# elmett_shield.net
KiCad netlist of a schematic drawn in EAGLE
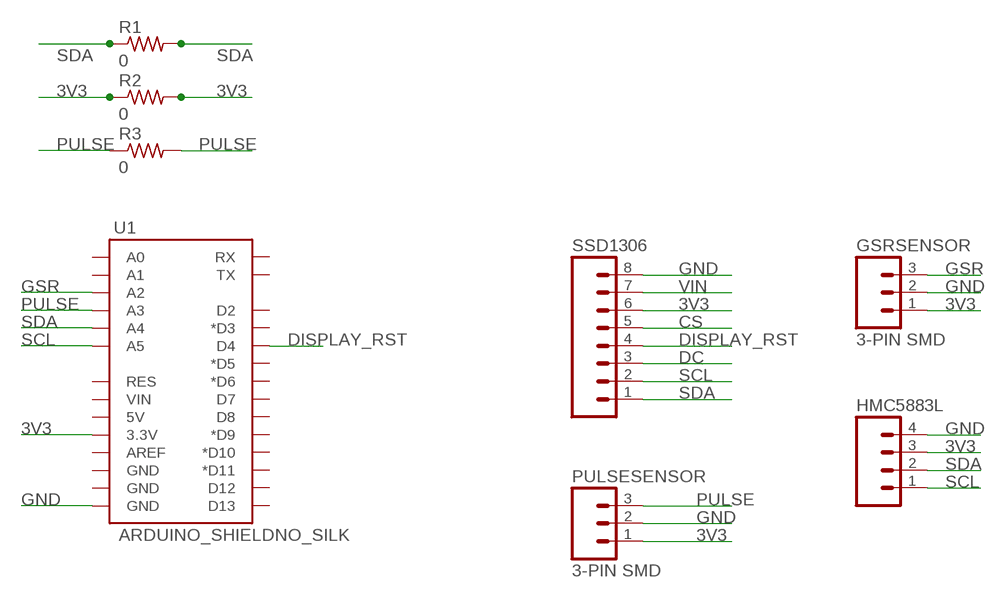
[diagram p0: schematic, sheet 1]

(export (version "E")
  (design (tool "Eeschema 10.0.6"))
  (components
    (comp (ref "GSRSENSOR")
      (value "3-PIN SMD")
      (footprint "eagle-import:JST-3-SMD")
      (libsource (lib "eagle-import") (part "M03JST-SMD"))
    )
    (comp (ref "HMC5883L")
      (value "M04PTH")
      (footprint "eagle-import:1X04")
      (libsource (lib "eagle-import") (part "M04PTH"))
    )
    (comp (ref "PULSESENSOR")
      (value "3-PIN SMD")
      (footprint "eagle-import:JST-3-SMD")
      (libsource (lib "eagle-import") (part "M03JST-SMD"))
    )
    (comp (ref "R1")
      (value "0")
      (footprint "eagle-import:1206")
      (libsource (lib "eagle-import") (part "RESISTOR1206"))
    )
    (comp (ref "R2")
      (value "0")
      (footprint "eagle-import:1206")
      (libsource (lib "eagle-import") (part "RESISTOR1206"))
    )
    (comp (ref "R3")
      (value "0")
      (footprint "eagle-import:1206")
      (libsource (lib "eagle-import") (part "RESISTOR1206"))
    )
    (comp (ref "SSD1306")
      (value "M08")
      (footprint "eagle-import:1X08_ROUND")
      (libsource (lib "eagle-import") (part "M08"))
    )
    (comp (ref "U1")
      (value "ARDUINO_SHIELDNO_SILK")
      (footprint "eagle-import:DUEMILANOVE_VIAS")
      (libsource (lib "eagle-import") (part "ARDUINO_SHIELDNO_SILK"))
    )
  )
  (nets
    (net (code "1") (name "/3V3") (class "Default")
      (node (ref "GSRSENSOR") (pin "1") (pinfunction "1_1") (pintype "passive"))
      (node (ref "HMC5883L") (pin "3") (pinfunction "3_3") (pintype "passive"))
      (node (ref "PULSESENSOR") (pin "1") (pinfunction "1_1") (pintype "passive"))
      (node (ref "R2") (pin "1") (pinfunction "1_1") (pintype "passive"))
      (node (ref "R2") (pin "2") (pinfunction "2_2") (pintype "passive"))
      (node (ref "SSD1306") (pin "6") (pinfunction "6_6") (pintype "passive"))
      (node (ref "U1") (pin "3.3V") (pinfunction "3.3V_3.3V") (pintype "bidirectional"))
    )
    (net (code "2") (name "/CS") (class "Default")
      (node (ref "SSD1306") (pin "5") (pinfunction "5_5") (pintype "passive"))
    )
    (net (code "3") (name "/DC") (class "Default")
      (node (ref "SSD1306") (pin "3") (pinfunction "3_3") (pintype "passive"))
    )
    (net (code "4") (name "/DISPLAY_RST") (class "Default")
      (node (ref "SSD1306") (pin "4") (pinfunction "4_4") (pintype "passive"))
      (node (ref "U1") (pin "D4") (pinfunction "D4_D4") (pintype "bidirectional"))
    )
    (net (code "5") (name "/GND") (class "Default")
      (node (ref "GSRSENSOR") (pin "2") (pinfunction "2_2") (pintype "passive"))
      (node (ref "HMC5883L") (pin "4") (pinfunction "4_4") (pintype "passive"))
      (node (ref "PULSESENSOR") (pin "2") (pinfunction "2_2") (pintype "passive"))
      (node (ref "SSD1306") (pin "8") (pinfunction "8_8") (pintype "passive"))
      (node (ref "U1") (pin "GND@0") (pinfunction "GND_GND@0") (pintype "bidirectional"))
    )
    (net (code "6") (name "/GSR") (class "Default")
      (node (ref "GSRSENSOR") (pin "3") (pinfunction "3_3") (pintype "passive"))
      (node (ref "U1") (pin "A2") (pinfunction "A2_A2") (pintype "bidirectional"))
    )
    (net (code "7") (name "/PULSE") (class "Default")
      (node (ref "PULSESENSOR") (pin "3") (pinfunction "3_3") (pintype "passive"))
      (node (ref "R3") (pin "1") (pinfunction "1_1") (pintype "passive"))
      (node (ref "R3") (pin "2") (pinfunction "2_2") (pintype "passive"))
      (node (ref "U1") (pin "A3") (pinfunction "A3_A3") (pintype "bidirectional"))
    )
    (net (code "8") (name "/SCL") (class "Default")
      (node (ref "HMC5883L") (pin "1") (pinfunction "1_1") (pintype "passive"))
      (node (ref "SSD1306") (pin "2") (pinfunction "2_2") (pintype "passive"))
      (node (ref "U1") (pin "A5") (pinfunction "A5_A5") (pintype "bidirectional"))
    )
    (net (code "9") (name "/SDA") (class "Default")
      (node (ref "HMC5883L") (pin "2") (pinfunction "2_2") (pintype "passive"))
      (node (ref "R1") (pin "1") (pinfunction "1_1") (pintype "passive"))
      (node (ref "R1") (pin "2") (pinfunction "2_2") (pintype "passive"))
      (node (ref "SSD1306") (pin "1") (pinfunction "1_1") (pintype "passive"))
      (node (ref "U1") (pin "A4") (pinfunction "A4_A4") (pintype "bidirectional"))
    )
    (net (code "10") (name "/VIN") (class "Default")
      (node (ref "SSD1306") (pin "7") (pinfunction "7_7") (pintype "passive"))
    )
    (net (code "11") (name "unconnected-(U1-*D3-PadD3)") (class "Default")
      (node (ref "U1") (pin "D3") (pinfunction "*D3_D3") (pintype "bidirectional"))
    )
    (net (code "12") (name "unconnected-(U1-*D5-PadD5)") (class "Default")
      (node (ref "U1") (pin "D5") (pinfunction "*D5_D5") (pintype "bidirectional"))
    )
    (net (code "13") (name "unconnected-(U1-*D6-PadD6)") (class "Default")
      (node (ref "U1") (pin "D6") (pinfunction "*D6_D6") (pintype "bidirectional"))
    )
    (net (code "14") (name "unconnected-(U1-*D9-PadD9)") (class "Default")
      (node (ref "U1") (pin "D9") (pinfunction "*D9_D9") (pintype "bidirectional"))
    )
    (net (code "15") (name "unconnected-(U1-*D10-PadD10)") (class "Default")
      (node (ref "U1") (pin "D10") (pinfunction "*D10_D10") (pintype "bidirectional"))
    )
    (net (code "16") (name "unconnected-(U1-*D11-PadD11)") (class "Default")
      (node (ref "U1") (pin "D11") (pinfunction "*D11_D11") (pintype "bidirectional"))
    )
    (net (code "17") (name "unconnected-(U1-GND-PadGND@1)") (class "Default")
      (node (ref "U1") (pin "GND@1") (pinfunction "GND_GND@1") (pintype "bidirectional"))
    )
    (net (code "18") (name "unconnected-(U1-GND-PadGND@2)") (class "Default")
      (node (ref "U1") (pin "GND@2") (pinfunction "GND_GND@2") (pintype "bidirectional"))
    )
    (net (code "19") (name "unconnected-(U1-Pad5V)") (class "Default")
      (node (ref "U1") (pin "5V") (pinfunction "5V_5V") (pintype "bidirectional"))
    )
    (net (code "20") (name "unconnected-(U1-PadA0)") (class "Default")
      (node (ref "U1") (pin "A0") (pinfunction "A0_A0") (pintype "bidirectional"))
    )
    (net (code "21") (name "unconnected-(U1-PadA1)") (class "Default")
      (node (ref "U1") (pin "A1") (pinfunction "A1_A1") (pintype "bidirectional"))
    )
    (net (code "22") (name "unconnected-(U1-PadAREF)") (class "Default")
      (node (ref "U1") (pin "AREF") (pinfunction "AREF_AREF") (pintype "bidirectional"))
    )
    (net (code "23") (name "unconnected-(U1-PadD2)") (class "Default")
      (node (ref "U1") (pin "D2") (pinfunction "D2_D2") (pintype "bidirectional"))
    )
    (net (code "24") (name "unconnected-(U1-PadD7)") (class "Default")
      (node (ref "U1") (pin "D7") (pinfunction "D7_D7") (pintype "bidirectional"))
    )
    (net (code "25") (name "unconnected-(U1-PadD8)") (class "Default")
      (node (ref "U1") (pin "D8") (pinfunction "D8_D8") (pintype "bidirectional"))
    )
    (net (code "26") (name "unconnected-(U1-PadD12)") (class "Default")
      (node (ref "U1") (pin "D12") (pinfunction "D12_D12") (pintype "bidirectional"))
    )
    (net (code "27") (name "unconnected-(U1-PadD13)") (class "Default")
      (node (ref "U1") (pin "D13") (pinfunction "D13_D13") (pintype "bidirectional"))
    )
    (net (code "28") (name "unconnected-(U1-PadRES)") (class "Default")
      (node (ref "U1") (pin "RES") (pinfunction "RES_RES") (pintype "bidirectional"))
    )
    (net (code "29") (name "unconnected-(U1-PadRX)") (class "Default")
      (node (ref "U1") (pin "RX") (pinfunction "RX_RX") (pintype "bidirectional"))
    )
    (net (code "30") (name "unconnected-(U1-PadTX)") (class "Default")
      (node (ref "U1") (pin "TX") (pinfunction "TX_TX") (pintype "bidirectional"))
    )
    (net (code "31") (name "unconnected-(U1-PadVIN)") (class "Default")
      (node (ref "U1") (pin "VIN") (pinfunction "VIN_VIN") (pintype "bidirectional"))
    )
  )
)
